# UD3_1_Gate_Driver.net
KiCad netlist of a schematic drawn in Altium Designer
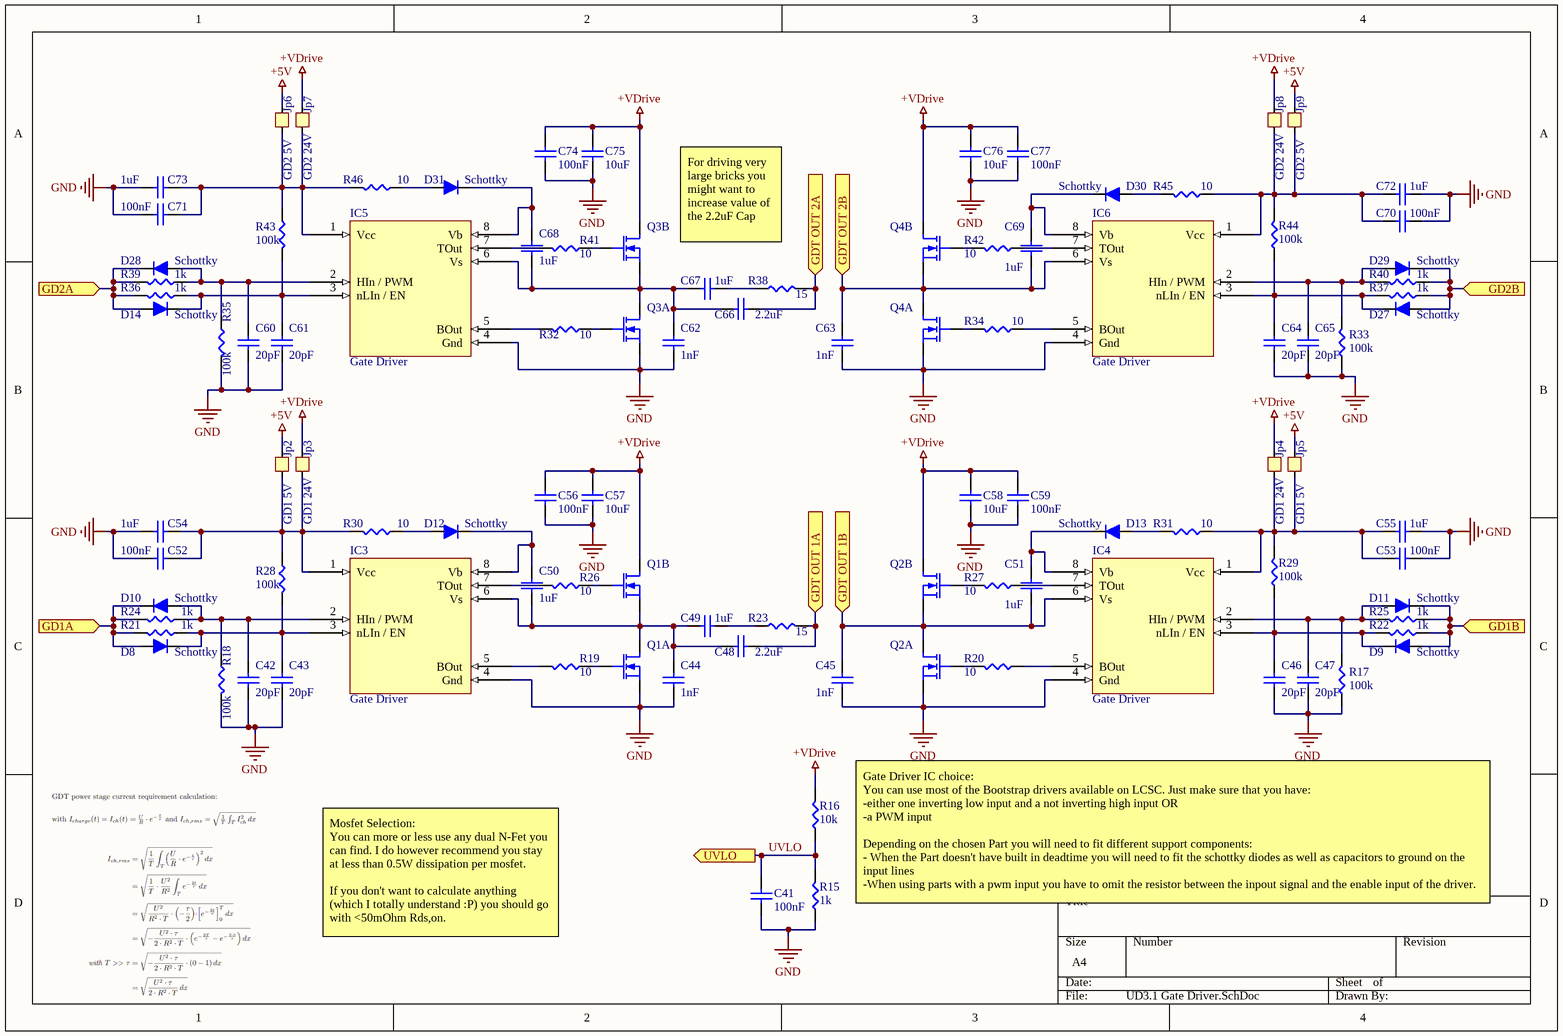
[diagram p0: UD3.1 Gate Driver.SchDoc]

(export (version "E")
  (design (tool "Eeschema 10.0.6"))
  (components
    (comp (ref "C41") (value "100nF") (footprint "0603") (libsource (lib "stdLib") (part "Cap")))
    (comp (ref "C42") (value "20pF") (footprint "0603") (libsource (lib "stdLib") (part "Cap")))
    (comp (ref "C43") (value "20pF") (footprint "0603") (libsource (lib "stdLib") (part "Cap")))
    (comp (ref "C44") (value "1nF") (footprint "0805") (libsource (lib "stdLib") (part "Cap")))
    (comp (ref "C45") (value "1nF") (footprint "0805") (libsource (lib "stdLib") (part "Cap")))
    (comp (ref "C46") (value "20pF") (footprint "0603") (libsource (lib "stdLib") (part "Cap")))
    (comp (ref "C47") (value "20pF") (footprint "0603") (libsource (lib "stdLib") (part "Cap")))
    (comp (ref "C48") (value "2.2uF") (footprint "1206") (libsource (lib "stdLib") (part "Cap")))
    (comp (ref "C49") (value "1uF") (footprint "1206") (libsource (lib "stdLib") (part "Cap")))
    (comp (ref "C50") (value "1uF") (footprint "0805") (libsource (lib "stdLib") (part "Cap")))
    (comp (ref "C51") (value "1uF") (footprint "0805") (libsource (lib "stdLib") (part "Cap")))
    (comp (ref "C52") (value "100nF") (footprint "0805") (libsource (lib "stdLib") (part "Cap")))
    (comp (ref "C53") (value "100nF") (footprint "0805") (libsource (lib "stdLib") (part "Cap")))
    (comp (ref "C54") (value "1uF") (footprint "0805") (libsource (lib "stdLib") (part "Cap")))
    (comp (ref "C55") (value "1uF") (footprint "0805") (libsource (lib "stdLib") (part "Cap")))
    (comp (ref "C56") (value "100nF") (footprint "0805") (libsource (lib "stdLib") (part "Cap")))
    (comp (ref "C57") (value "10uF") (footprint "0805") (libsource (lib "stdLib") (part "Cap")))
    (comp (ref "C58") (value "10uF") (footprint "0805") (libsource (lib "stdLib") (part "Cap")))
    (comp (ref "C59") (value "100nF") (footprint "0805") (libsource (lib "stdLib") (part "Cap")))
    (comp (ref "C60") (value "20pF") (footprint "0603") (libsource (lib "stdLib") (part "Cap")))
    (comp (ref "C61") (value "20pF") (footprint "0603") (libsource (lib "stdLib") (part "Cap")))
    (comp (ref "C62") (value "1nF") (footprint "0805") (libsource (lib "stdLib") (part "Cap")))
    (comp (ref "C63") (value "1nF") (footprint "0805") (libsource (lib "stdLib") (part "Cap")))
    (comp (ref "C64") (value "20pF") (footprint "0603") (libsource (lib "stdLib") (part "Cap")))
    (comp (ref "C65") (value "20pF") (footprint "0603") (libsource (lib "stdLib") (part "Cap")))
    (comp (ref "C66") (value "2.2uF") (footprint "1206") (libsource (lib "stdLib") (part "Cap")))
    (comp (ref "C67") (value "1uF") (footprint "1206") (libsource (lib "stdLib") (part "Cap")))
    (comp (ref "C68") (value "1uF") (footprint "0805") (libsource (lib "stdLib") (part "Cap")))
    (comp (ref "C69") (value "1uF") (footprint "0805") (libsource (lib "stdLib") (part "Cap")))
    (comp (ref "C70") (value "100nF") (footprint "0805") (libsource (lib "stdLib") (part "Cap")))
    (comp (ref "C71") (value "100nF") (footprint "0805") (libsource (lib "stdLib") (part "Cap")))
    (comp (ref "C72") (value "1uF") (footprint "0805") (libsource (lib "stdLib") (part "Cap")))
    (comp (ref "C73") (value "1uF") (footprint "0805") (libsource (lib "stdLib") (part "Cap")))
    (comp (ref "C74") (value "100nF") (footprint "0805") (libsource (lib "stdLib") (part "Cap")))
    (comp (ref "C75") (value "10uF") (footprint "0805") (libsource (lib "stdLib") (part "Cap")))
    (comp (ref "C76") (value "10uF") (footprint "0805") (libsource (lib "stdLib") (part "Cap")))
    (comp (ref "C77") (value "100nF") (footprint "0805") (libsource (lib "stdLib") (part "Cap")))
    (comp (ref "D8")
      (value "Schottky")
      (footprint "SOD523")
      (description "Cmon its a diode what more do I need to say?")
      (libsource (lib "stdLib") (part "Diode"))
    )
    (comp (ref "D9")
      (value "Schottky")
      (footprint "SOD523")
      (description "Cmon its a diode what more do I need to say?")
      (libsource (lib "stdLib") (part "Diode"))
    )
    (comp (ref "D10")
      (value "Schottky")
      (footprint "SOD523")
      (description "Cmon its a diode what more do I need to say?")
      (libsource (lib "stdLib") (part "Diode"))
    )
    (comp (ref "D11")
      (value "Schottky")
      (footprint "SOD523")
      (description "Cmon its a diode what more do I need to say?")
      (libsource (lib "stdLib") (part "Diode"))
    )
    (comp (ref "D12")
      (value "Schottky")
      (footprint "SOD523")
      (description "Cmon its a diode what more do I need to say?")
      (libsource (lib "stdLib") (part "Diode"))
    )
    (comp (ref "D13")
      (value "Schottky")
      (footprint "SOD523")
      (description "Cmon its a diode what more do I need to say?")
      (libsource (lib "stdLib") (part "Diode"))
    )
    (comp (ref "D14")
      (value "Schottky")
      (footprint "SOD523")
      (description "Cmon its a diode what more do I need to say?")
      (libsource (lib "stdLib") (part "Diode"))
    )
    (comp (ref "D27")
      (value "Schottky")
      (footprint "SOD523")
      (description "Cmon its a diode what more do I need to say?")
      (libsource (lib "stdLib") (part "Diode"))
    )
    (comp (ref "D28")
      (value "Schottky")
      (footprint "SOD523")
      (description "Cmon its a diode what more do I need to say?")
      (libsource (lib "stdLib") (part "Diode"))
    )
    (comp (ref "D29")
      (value "Schottky")
      (footprint "SOD523")
      (description "Cmon its a diode what more do I need to say?")
      (libsource (lib "stdLib") (part "Diode"))
    )
    (comp (ref "D30")
      (value "Schottky")
      (footprint "SOD523")
      (description "Cmon its a diode what more do I need to say?")
      (libsource (lib "stdLib") (part "Diode"))
    )
    (comp (ref "D31")
      (value "Schottky")
      (footprint "SOD523")
      (description "Cmon its a diode what more do I need to say?")
      (libsource (lib "stdLib") (part "Diode"))
    )
    (comp (ref "IC3")
      (value "Gate Driver")
      (footprint "SOIC8")
      (description "Bootstrappable half bridge driver IC")
      (libsource (lib "") (part "Gatedriver Bootstrap_1"))
    )
    (comp (ref "IC4")
      (value "Gate Driver")
      (footprint "SOIC8")
      (description "Bootstrappable half bridge driver IC")
      (libsource (lib "stdLib") (part "Gatedriver Bootstrap"))
    )
    (comp (ref "IC5")
      (value "Gate Driver")
      (footprint "SOIC8")
      (description "Bootstrappable half bridge driver IC")
      (libsource (lib "") (part "Gatedriver Bootstrap_1"))
    )
    (comp (ref "IC6")
      (value "Gate Driver")
      (footprint "SOIC8")
      (description "Bootstrappable half bridge driver IC")
      (libsource (lib "stdLib") (part "Gatedriver Bootstrap"))
    )
    (comp (ref "Jp2") (value "GD1 5V") (footprint "PCB Jumper NO") (libsource (lib "stdLib") (part "Jumper")))
    (comp (ref "Jp3")
      (value "GD1 24V")
      (footprint "PCB Jumper NO")
      (libsource (lib "stdLib") (part "Jumper"))
    )
    (comp (ref "Jp4") (value "GD1 24V") (footprint "PCB Jumper NO") (libsource (lib "") (part "Jumper_1")))
    (comp (ref "Jp5") (value "GD1 5V") (footprint "PCB Jumper NO") (libsource (lib "") (part "Jumper_1")))
    (comp (ref "Jp6") (value "GD2 5V") (footprint "PCB Jumper NO") (libsource (lib "stdLib") (part "Jumper")))
    (comp (ref "Jp7")
      (value "GD2 24V")
      (footprint "PCB Jumper NO")
      (libsource (lib "stdLib") (part "Jumper"))
    )
    (comp (ref "Jp8") (value "GD2 24V") (footprint "PCB Jumper NO") (libsource (lib "") (part "Jumper_1")))
    (comp (ref "Jp9") (value "GD2 5V") (footprint "PCB Jumper NO") (libsource (lib "") (part "Jumper_1")))
    (comp (ref "Q1")
      (value "Dual NFet")
      (footprint "SO-8FL - Dual")
      (description "Dual Mosfet, two N channel")
      (libsource (lib "stdLib") (part "Mosfet 2N"))
    )
    (comp (ref "Q2")
      (value "Dual NFet")
      (footprint "SO-8FL - Dual")
      (description "Dual Mosfet, two N channel")
      (libsource (lib "stdLib") (part "Mosfet 2N"))
    )
    (comp (ref "Q3")
      (value "Dual NFet")
      (footprint "SO-8FL - Dual")
      (description "Dual Mosfet, two N channel")
      (libsource (lib "stdLib") (part "Mosfet 2N"))
    )
    (comp (ref "Q4")
      (value "Dual NFet")
      (footprint "SO-8FL - Dual")
      (description "Dual Mosfet, two N channel")
      (libsource (lib "stdLib") (part "Mosfet 2N"))
    )
    (comp (ref "R15") (value "1k") (footprint "0603") (libsource (lib "stdLib") (part "Resistor")))
    (comp (ref "R16") (value "10k") (footprint "0603") (libsource (lib "stdLib") (part "Resistor")))
    (comp (ref "R17") (value "100k") (footprint "0603") (libsource (lib "stdLib") (part "Resistor")))
    (comp (ref "R18") (value "100k") (footprint "0603") (libsource (lib "stdLib") (part "Resistor")))
    (comp (ref "R19") (value "10") (footprint "0805") (libsource (lib "stdLib") (part "Resistor")))
    (comp (ref "R20") (value "10") (footprint "0805") (libsource (lib "stdLib") (part "Resistor")))
    (comp (ref "R21") (value "1k") (footprint "0603") (libsource (lib "stdLib") (part "Resistor")))
    (comp (ref "R22") (value "1k") (footprint "0603") (libsource (lib "stdLib") (part "Resistor")))
    (comp (ref "R23") (value "15") (footprint "1206") (libsource (lib "stdLib") (part "Resistor")))
    (comp (ref "R24") (value "1k") (footprint "0603") (libsource (lib "stdLib") (part "Resistor")))
    (comp (ref "R25") (value "1k") (footprint "0603") (libsource (lib "stdLib") (part "Resistor")))
    (comp (ref "R26") (value "10") (footprint "0805") (libsource (lib "stdLib") (part "Resistor")))
    (comp (ref "R27") (value "10") (footprint "0805") (libsource (lib "stdLib") (part "Resistor")))
    (comp (ref "R28") (value "100k") (footprint "0603") (libsource (lib "stdLib") (part "Resistor")))
    (comp (ref "R29") (value "100k") (footprint "0603") (libsource (lib "stdLib") (part "Resistor")))
    (comp (ref "R30") (value "10") (footprint "0603") (libsource (lib "stdLib") (part "Resistor")))
    (comp (ref "R31") (value "10") (footprint "0603") (libsource (lib "stdLib") (part "Resistor")))
    (comp (ref "R32") (value "10") (footprint "0805") (libsource (lib "stdLib") (part "Resistor")))
    (comp (ref "R33") (value "100k") (footprint "0603") (libsource (lib "stdLib") (part "Resistor")))
    (comp (ref "R34") (value "10") (footprint "0805") (libsource (lib "stdLib") (part "Resistor")))
    (comp (ref "R35") (value "100k") (footprint "0603") (libsource (lib "stdLib") (part "Resistor")))
    (comp (ref "R36") (value "1k") (footprint "0603") (libsource (lib "stdLib") (part "Resistor")))
    (comp (ref "R37") (value "1k") (footprint "0603") (libsource (lib "stdLib") (part "Resistor")))
    (comp (ref "R38") (value "15") (footprint "1206") (libsource (lib "stdLib") (part "Resistor")))
    (comp (ref "R39") (value "1k") (footprint "0603") (libsource (lib "stdLib") (part "Resistor")))
    (comp (ref "R40") (value "1k") (footprint "0603") (libsource (lib "stdLib") (part "Resistor")))
    (comp (ref "R41") (value "10") (footprint "0805") (libsource (lib "stdLib") (part "Resistor")))
    (comp (ref "R42") (value "10") (footprint "0805") (libsource (lib "stdLib") (part "Resistor")))
    (comp (ref "R43") (value "100k") (footprint "0603") (libsource (lib "stdLib") (part "Resistor")))
    (comp (ref "R44") (value "100k") (footprint "0603") (libsource (lib "stdLib") (part "Resistor")))
    (comp (ref "R45") (value "10") (footprint "0603") (libsource (lib "stdLib") (part "Resistor")))
    (comp (ref "R46") (value "10") (footprint "0603") (libsource (lib "stdLib") (part "Resistor")))
  )
  (nets
    (net (code "1") (name "+5V") (class "Default")
      (node (ref "Jp2") (pin "2") (pinfunction "2_2") (pintype "passive"))
      (node (ref "Jp5") (pin "2") (pinfunction "2_2") (pintype "passive"))
      (node (ref "Jp6") (pin "2") (pinfunction "2_2") (pintype "passive"))
      (node (ref "Jp9") (pin "2") (pinfunction "2_2") (pintype "passive"))
    )
    (net (code "2") (name "+VDrive") (class "Default")
      (node (ref "C56") (pin "2") (pinfunction "2_2") (pintype "passive"))
      (node (ref "C57") (pin "2") (pinfunction "2_2") (pintype "passive"))
      (node (ref "C58") (pin "2") (pinfunction "2_2") (pintype "passive"))
      (node (ref "C59") (pin "2") (pinfunction "2_2") (pintype "passive"))
      (node (ref "C74") (pin "2") (pinfunction "2_2") (pintype "passive"))
      (node (ref "C75") (pin "2") (pinfunction "2_2") (pintype "passive"))
      (node (ref "C76") (pin "2") (pinfunction "2_2") (pintype "passive"))
      (node (ref "C77") (pin "2") (pinfunction "2_2") (pintype "passive"))
      (node (ref "Jp3") (pin "2") (pinfunction "2_2") (pintype "passive"))
      (node (ref "Jp4") (pin "2") (pinfunction "2_2") (pintype "passive"))
      (node (ref "Jp7") (pin "2") (pinfunction "2_2") (pintype "passive"))
      (node (ref "Jp8") (pin "2") (pinfunction "2_2") (pintype "passive"))
      (node (ref "Q1") (pin "D1") (pinfunction "D1_D1") (pintype "passive"))
      (node (ref "Q2") (pin "D1") (pinfunction "D1_D1") (pintype "passive"))
      (node (ref "Q3") (pin "D1") (pinfunction "D1_D1") (pintype "passive"))
      (node (ref "Q4") (pin "D1") (pinfunction "D1_D1") (pintype "passive"))
      (node (ref "R16") (pin "1") (pinfunction "1_1") (pintype "passive"))
    )
    (net (code "3") (name "/GD1A") (class "Default")
      (node (ref "D10") (pin "2") (pintype "passive"))
      (node (ref "D8") (pin "1") (pintype "passive"))
      (node (ref "R21") (pin "1") (pinfunction "1_1") (pintype "passive"))
      (node (ref "R24") (pin "1") (pinfunction "1_1") (pintype "passive"))
    )
    (net (code "4") (name "/GD1B") (class "Default")
      (node (ref "D11") (pin "2") (pintype "passive"))
      (node (ref "D9") (pin "1") (pintype "passive"))
      (node (ref "R22") (pin "1") (pinfunction "1_1") (pintype "passive"))
      (node (ref "R25") (pin "1") (pinfunction "1_1") (pintype "passive"))
    )
    (net (code "5") (name "/GD2A") (class "Default")
      (node (ref "D14") (pin "1") (pintype "passive"))
      (node (ref "D28") (pin "2") (pintype "passive"))
      (node (ref "R36") (pin "1") (pinfunction "1_1") (pintype "passive"))
      (node (ref "R39") (pin "1") (pinfunction "1_1") (pintype "passive"))
    )
    (net (code "6") (name "/GD2B") (class "Default")
      (node (ref "D27") (pin "1") (pintype "passive"))
      (node (ref "D29") (pin "2") (pintype "passive"))
      (node (ref "R37") (pin "1") (pinfunction "1_1") (pintype "passive"))
      (node (ref "R40") (pin "1") (pinfunction "1_1") (pintype "passive"))
    )
    (net (code "7") (name "/GDT OUT 1A") (class "Default")
      (node (ref "C48") (pin "2") (pinfunction "2_2") (pintype "passive"))
      (node (ref "R23") (pin "2") (pinfunction "2_2") (pintype "passive"))
    )
    (net (code "8") (name "/GDT OUT 1B") (class "Default")
      (node (ref "C45") (pin "2") (pinfunction "2_2") (pintype "passive"))
      (node (ref "C51") (pin "1") (pinfunction "1_1") (pintype "passive"))
      (node (ref "IC4") (pin "6") (pinfunction "Vs_6") (pintype "input"))
      (node (ref "Q2") (pin "D2") (pinfunction "D2_D2") (pintype "passive"))
      (node (ref "Q2") (pin "S1") (pinfunction "S1_S1") (pintype "passive"))
    )
    (net (code "9") (name "/GDT OUT 2A") (class "Default")
      (node (ref "C66") (pin "2") (pinfunction "2_2") (pintype "passive"))
      (node (ref "R38") (pin "2") (pinfunction "2_2") (pintype "passive"))
    )
    (net (code "10") (name "/GDT OUT 2B") (class "Default")
      (node (ref "C63") (pin "2") (pinfunction "2_2") (pintype "passive"))
      (node (ref "C69") (pin "1") (pinfunction "1_1") (pintype "passive"))
      (node (ref "IC6") (pin "6") (pinfunction "Vs_6") (pintype "input"))
      (node (ref "Q4") (pin "D2") (pinfunction "D2_D2") (pintype "passive"))
      (node (ref "Q4") (pin "S1") (pinfunction "S1_S1") (pintype "passive"))
    )
    (net (code "11") (name "/UVLO") (class "Default")
      (node (ref "C41") (pin "2") (pinfunction "2_2") (pintype "passive"))
      (node (ref "R15") (pin "1") (pinfunction "1_1") (pintype "passive"))
      (node (ref "R16") (pin "2") (pinfunction "2_2") (pintype "passive"))
    )
    (net (code "12") (name "GND") (class "Default")
      (node (ref "C41") (pin "1") (pinfunction "1_1") (pintype "passive"))
      (node (ref "C42") (pin "2") (pinfunction "2_2") (pintype "passive"))
      (node (ref "C43") (pin "2") (pinfunction "2_2") (pintype "passive"))
      (node (ref "C44") (pin "1") (pinfunction "1_1") (pintype "passive"))
      (node (ref "C45") (pin "1") (pinfunction "1_1") (pintype "passive"))
      (node (ref "C46") (pin "2") (pinfunction "2_2") (pintype "passive"))
      (node (ref "C47") (pin "2") (pinfunction "2_2") (pintype "passive"))
      (node (ref "C52") (pin "2") (pinfunction "2_2") (pintype "passive"))
      (node (ref "C53") (pin "2") (pinfunction "2_2") (pintype "passive"))
      (node (ref "C54") (pin "2") (pinfunction "2_2") (pintype "passive"))
      (node (ref "C55") (pin "2") (pinfunction "2_2") (pintype "passive"))
      (node (ref "C56") (pin "1") (pinfunction "1_1") (pintype "passive"))
      (node (ref "C57") (pin "1") (pinfunction "1_1") (pintype "passive"))
      (node (ref "C58") (pin "1") (pinfunction "1_1") (pintype "passive"))
      (node (ref "C59") (pin "1") (pinfunction "1_1") (pintype "passive"))
      (node (ref "C60") (pin "2") (pinfunction "2_2") (pintype "passive"))
      (node (ref "C61") (pin "2") (pinfunction "2_2") (pintype "passive"))
      (node (ref "C62") (pin "1") (pinfunction "1_1") (pintype "passive"))
      (node (ref "C63") (pin "1") (pinfunction "1_1") (pintype "passive"))
      (node (ref "C64") (pin "2") (pinfunction "2_2") (pintype "passive"))
      (node (ref "C65") (pin "2") (pinfunction "2_2") (pintype "passive"))
      (node (ref "C70") (pin "2") (pinfunction "2_2") (pintype "passive"))
      (node (ref "C71") (pin "2") (pinfunction "2_2") (pintype "passive"))
      (node (ref "C72") (pin "2") (pinfunction "2_2") (pintype "passive"))
      (node (ref "C73") (pin "2") (pinfunction "2_2") (pintype "passive"))
      (node (ref "C74") (pin "1") (pinfunction "1_1") (pintype "passive"))
      (node (ref "C75") (pin "1") (pinfunction "1_1") (pintype "passive"))
      (node (ref "C76") (pin "1") (pinfunction "1_1") (pintype "passive"))
      (node (ref "C77") (pin "1") (pinfunction "1_1") (pintype "passive"))
      (node (ref "IC3") (pin "4") (pinfunction "Gnd_4") (pintype "input"))
      (node (ref "IC4") (pin "4") (pinfunction "Gnd_4") (pintype "input"))
      (node (ref "IC5") (pin "4") (pinfunction "Gnd_4") (pintype "input"))
      (node (ref "IC6") (pin "4") (pinfunction "Gnd_4") (pintype "input"))
      (node (ref "Q1") (pin "S2") (pinfunction "S2_S2") (pintype "passive"))
      (node (ref "Q2") (pin "S2") (pinfunction "S2_S2") (pintype "passive"))
      (node (ref "Q3") (pin "S2") (pinfunction "S2_S2") (pintype "passive"))
      (node (ref "Q4") (pin "S2") (pinfunction "S2_S2") (pintype "passive"))
      (node (ref "R15") (pin "2") (pinfunction "2_2") (pintype "passive"))
      (node (ref "R17") (pin "1") (pinfunction "1_1") (pintype "passive"))
      (node (ref "R18") (pin "1") (pinfunction "1_1") (pintype "passive"))
      (node (ref "R33") (pin "1") (pinfunction "1_1") (pintype "passive"))
      (node (ref "R35") (pin "1") (pinfunction "1_1") (pintype "passive"))
    )
    (net (code "13") (name "Net-(C49-Pad2)") (class "Default")
      (node (ref "C49") (pin "2") (pinfunction "2_2") (pintype "passive"))
      (node (ref "R23") (pin "1") (pinfunction "1_1") (pintype "passive"))
    )
    (net (code "14") (name "Net-(C67-Pad2)") (class "Default")
      (node (ref "C67") (pin "2") (pinfunction "2_2") (pintype "passive"))
      (node (ref "R38") (pin "1") (pinfunction "1_1") (pintype "passive"))
    )
    (net (code "15") (name "Net-(D12-Pad1)") (class "Default")
      (node (ref "D12") (pin "1") (pintype "passive"))
      (node (ref "R30") (pin "2") (pinfunction "2_2") (pintype "passive"))
    )
    (net (code "16") (name "Net-(D13-Pad1)") (class "Default")
      (node (ref "D13") (pin "1") (pintype "passive"))
      (node (ref "R31") (pin "2") (pinfunction "2_2") (pintype "passive"))
    )
    (net (code "17") (name "Net-(D30-Pad1)") (class "Default")
      (node (ref "D30") (pin "1") (pintype "passive"))
      (node (ref "R45") (pin "2") (pinfunction "2_2") (pintype "passive"))
    )
    (net (code "18") (name "Net-(D31-Pad1)") (class "Default")
      (node (ref "D31") (pin "1") (pintype "passive"))
      (node (ref "R46") (pin "2") (pinfunction "2_2") (pintype "passive"))
    )
    (net (code "19") (name "Net-(IC3-BOut)") (class "Default")
      (node (ref "IC3") (pin "5") (pinfunction "BOut_5") (pintype "input"))
      (node (ref "R19") (pin "1") (pinfunction "1_1") (pintype "passive"))
    )
    (net (code "20") (name "Net-(IC3-HIn_{slash}_PWM)") (class "Default")
      (node (ref "C42") (pin "1") (pinfunction "1_1") (pintype "passive"))
      (node (ref "D10") (pin "1") (pintype "passive"))
      (node (ref "IC3") (pin "2") (pinfunction "HIn_/_PWM_2") (pintype "input"))
      (node (ref "R18") (pin "2") (pinfunction "2_2") (pintype "passive"))
      (node (ref "R24") (pin "2") (pinfunction "2_2") (pintype "passive"))
    )
    (net (code "21") (name "Net-(IC3-TOut)") (class "Default")
      (node (ref "IC3") (pin "7") (pinfunction "TOut_7") (pintype "input"))
      (node (ref "R26") (pin "1") (pinfunction "1_1") (pintype "passive"))
    )
    (net (code "22") (name "Net-(IC3-Vb)") (class "Default")
      (node (ref "C50") (pin "2") (pinfunction "2_2") (pintype "passive"))
      (node (ref "D12") (pin "2") (pintype "passive"))
      (node (ref "IC3") (pin "8") (pinfunction "Vb_8") (pintype "input"))
    )
    (net (code "23") (name "Net-(IC3-Vcc)") (class "Default")
      (node (ref "C52") (pin "1") (pinfunction "1_1") (pintype "passive"))
      (node (ref "C54") (pin "1") (pinfunction "1_1") (pintype "passive"))
      (node (ref "IC3") (pin "1") (pinfunction "Vcc_1") (pintype "input"))
      (node (ref "Jp2") (pin "1") (pinfunction "1_1") (pintype "passive"))
      (node (ref "Jp3") (pin "1") (pinfunction "1_1") (pintype "passive"))
      (node (ref "R28") (pin "2") (pinfunction "2_2") (pintype "passive"))
      (node (ref "R30") (pin "1") (pinfunction "1_1") (pintype "passive"))
    )
    (net (code "24") (name "Net-(IC3-Vs)") (class "Default")
      (node (ref "C44") (pin "2") (pinfunction "2_2") (pintype "passive"))
      (node (ref "C48") (pin "1") (pinfunction "1_1") (pintype "passive"))
      (node (ref "C49") (pin "1") (pinfunction "1_1") (pintype "passive"))
      (node (ref "C50") (pin "1") (pinfunction "1_1") (pintype "passive"))
      (node (ref "IC3") (pin "6") (pinfunction "Vs_6") (pintype "input"))
      (node (ref "Q1") (pin "D2") (pinfunction "D2_D2") (pintype "passive"))
      (node (ref "Q1") (pin "S1") (pinfunction "S1_S1") (pintype "passive"))
    )
    (net (code "25") (name "Net-(IC3-nLIn_{slash}_EN)") (class "Default")
      (node (ref "C43") (pin "1") (pinfunction "1_1") (pintype "passive"))
      (node (ref "D8") (pin "2") (pintype "passive"))
      (node (ref "IC3") (pin "3") (pinfunction "nLIn_/_EN_3") (pintype "input"))
      (node (ref "R21") (pin "2") (pinfunction "2_2") (pintype "passive"))
      (node (ref "R28") (pin "1") (pinfunction "1_1") (pintype "passive"))
    )
    (net (code "26") (name "Net-(IC4-BOut)") (class "Default")
      (node (ref "IC4") (pin "5") (pinfunction "BOut_5") (pintype "input"))
      (node (ref "R20") (pin "1") (pinfunction "1_1") (pintype "passive"))
    )
    (net (code "27") (name "Net-(IC4-HIn_{slash}_PWM)") (class "Default")
      (node (ref "C47") (pin "1") (pinfunction "1_1") (pintype "passive"))
      (node (ref "D11") (pin "1") (pintype "passive"))
      (node (ref "IC4") (pin "2") (pinfunction "HIn_/_PWM_2") (pintype "input"))
      (node (ref "R17") (pin "2") (pinfunction "2_2") (pintype "passive"))
      (node (ref "R25") (pin "2") (pinfunction "2_2") (pintype "passive"))
    )
    (net (code "28") (name "Net-(IC4-TOut)") (class "Default")
      (node (ref "IC4") (pin "7") (pinfunction "TOut_7") (pintype "input"))
      (node (ref "R27") (pin "1") (pinfunction "1_1") (pintype "passive"))
    )
    (net (code "29") (name "Net-(IC4-Vb)") (class "Default")
      (node (ref "C51") (pin "2") (pinfunction "2_2") (pintype "passive"))
      (node (ref "D13") (pin "2") (pintype "passive"))
      (node (ref "IC4") (pin "8") (pinfunction "Vb_8") (pintype "input"))
    )
    (net (code "30") (name "Net-(IC4-Vcc)") (class "Default")
      (node (ref "C53") (pin "1") (pinfunction "1_1") (pintype "passive"))
      (node (ref "C55") (pin "1") (pinfunction "1_1") (pintype "passive"))
      (node (ref "IC4") (pin "1") (pinfunction "Vcc_1") (pintype "input"))
      (node (ref "Jp4") (pin "1") (pinfunction "1_1") (pintype "passive"))
      (node (ref "Jp5") (pin "1") (pinfunction "1_1") (pintype "passive"))
      (node (ref "R29") (pin "2") (pinfunction "2_2") (pintype "passive"))
      (node (ref "R31") (pin "1") (pinfunction "1_1") (pintype "passive"))
    )
    (net (code "31") (name "Net-(IC4-nLIn_{slash}_EN)") (class "Default")
      (node (ref "C46") (pin "1") (pinfunction "1_1") (pintype "passive"))
      (node (ref "D9") (pin "2") (pintype "passive"))
      (node (ref "IC4") (pin "3") (pinfunction "nLIn_/_EN_3") (pintype "input"))
      (node (ref "R22") (pin "2") (pinfunction "2_2") (pintype "passive"))
      (node (ref "R29") (pin "1") (pinfunction "1_1") (pintype "passive"))
    )
    (net (code "32") (name "Net-(IC5-BOut)") (class "Default")
      (node (ref "IC5") (pin "5") (pinfunction "BOut_5") (pintype "input"))
      (node (ref "R32") (pin "1") (pinfunction "1_1") (pintype "passive"))
    )
    (net (code "33") (name "Net-(IC5-HIn_{slash}_PWM)") (class "Default")
      (node (ref "C60") (pin "1") (pinfunction "1_1") (pintype "passive"))
      (node (ref "D28") (pin "1") (pintype "passive"))
      (node (ref "IC5") (pin "2") (pinfunction "HIn_/_PWM_2") (pintype "input"))
      (node (ref "R35") (pin "2") (pinfunction "2_2") (pintype "passive"))
      (node (ref "R39") (pin "2") (pinfunction "2_2") (pintype "passive"))
    )
    (net (code "34") (name "Net-(IC5-TOut)") (class "Default")
      (node (ref "IC5") (pin "7") (pinfunction "TOut_7") (pintype "input"))
      (node (ref "R41") (pin "1") (pinfunction "1_1") (pintype "passive"))
    )
    (net (code "35") (name "Net-(IC5-Vb)") (class "Default")
      (node (ref "C68") (pin "2") (pinfunction "2_2") (pintype "passive"))
      (node (ref "D31") (pin "2") (pintype "passive"))
      (node (ref "IC5") (pin "8") (pinfunction "Vb_8") (pintype "input"))
    )
    (net (code "36") (name "Net-(IC5-Vcc)") (class "Default")
      (node (ref "C71") (pin "1") (pinfunction "1_1") (pintype "passive"))
      (node (ref "C73") (pin "1") (pinfunction "1_1") (pintype "passive"))
      (node (ref "IC5") (pin "1") (pinfunction "Vcc_1") (pintype "input"))
      (node (ref "Jp6") (pin "1") (pinfunction "1_1") (pintype "passive"))
      (node (ref "Jp7") (pin "1") (pinfunction "1_1") (pintype "passive"))
      (node (ref "R43") (pin "2") (pinfunction "2_2") (pintype "passive"))
      (node (ref "R46") (pin "1") (pinfunction "1_1") (pintype "passive"))
    )
    (net (code "37") (name "Net-(IC5-Vs)") (class "Default")
      (node (ref "C62") (pin "2") (pinfunction "2_2") (pintype "passive"))
      (node (ref "C66") (pin "1") (pinfunction "1_1") (pintype "passive"))
      (node (ref "C67") (pin "1") (pinfunction "1_1") (pintype "passive"))
      (node (ref "C68") (pin "1") (pinfunction "1_1") (pintype "passive"))
      (node (ref "IC5") (pin "6") (pinfunction "Vs_6") (pintype "input"))
      (node (ref "Q3") (pin "D2") (pinfunction "D2_D2") (pintype "passive"))
      (node (ref "Q3") (pin "S1") (pinfunction "S1_S1") (pintype "passive"))
    )
    (net (code "38") (name "Net-(IC5-nLIn_{slash}_EN)") (class "Default")
      (node (ref "C61") (pin "1") (pinfunction "1_1") (pintype "passive"))
      (node (ref "D14") (pin "2") (pintype "passive"))
      (node (ref "IC5") (pin "3") (pinfunction "nLIn_/_EN_3") (pintype "input"))
      (node (ref "R36") (pin "2") (pinfunction "2_2") (pintype "passive"))
      (node (ref "R43") (pin "1") (pinfunction "1_1") (pintype "passive"))
    )
    (net (code "39") (name "Net-(IC6-BOut)") (class "Default")
      (node (ref "IC6") (pin "5") (pinfunction "BOut_5") (pintype "input"))
      (node (ref "R34") (pin "1") (pinfunction "1_1") (pintype "passive"))
    )
    (net (code "40") (name "Net-(IC6-HIn_{slash}_PWM)") (class "Default")
      (node (ref "C65") (pin "1") (pinfunction "1_1") (pintype "passive"))
      (node (ref "D29") (pin "1") (pintype "passive"))
      (node (ref "IC6") (pin "2") (pinfunction "HIn_/_PWM_2") (pintype "input"))
      (node (ref "R33") (pin "2") (pinfunction "2_2") (pintype "passive"))
      (node (ref "R40") (pin "2") (pinfunction "2_2") (pintype "passive"))
    )
    (net (code "41") (name "Net-(IC6-TOut)") (class "Default")
      (node (ref "IC6") (pin "7") (pinfunction "TOut_7") (pintype "input"))
      (node (ref "R42") (pin "1") (pinfunction "1_1") (pintype "passive"))
    )
    (net (code "42") (name "Net-(IC6-Vb)") (class "Default")
      (node (ref "C69") (pin "2") (pinfunction "2_2") (pintype "passive"))
      (node (ref "D30") (pin "2") (pintype "passive"))
      (node (ref "IC6") (pin "8") (pinfunction "Vb_8") (pintype "input"))
    )
    (net (code "43") (name "Net-(IC6-Vcc)") (class "Default")
      (node (ref "C70") (pin "1") (pinfunction "1_1") (pintype "passive"))
      (node (ref "C72") (pin "1") (pinfunction "1_1") (pintype "passive"))
      (node (ref "IC6") (pin "1") (pinfunction "Vcc_1") (pintype "input"))
      (node (ref "Jp8") (pin "1") (pinfunction "1_1") (pintype "passive"))
      (node (ref "Jp9") (pin "1") (pinfunction "1_1") (pintype "passive"))
      (node (ref "R44") (pin "2") (pinfunction "2_2") (pintype "passive"))
      (node (ref "R45") (pin "1") (pinfunction "1_1") (pintype "passive"))
    )
    (net (code "44") (name "Net-(IC6-nLIn_{slash}_EN)") (class "Default")
      (node (ref "C64") (pin "1") (pinfunction "1_1") (pintype "passive"))
      (node (ref "D27") (pin "2") (pintype "passive"))
      (node (ref "IC6") (pin "3") (pinfunction "nLIn_/_EN_3") (pintype "input"))
      (node (ref "R37") (pin "2") (pinfunction "2_2") (pintype "passive"))
      (node (ref "R44") (pin "1") (pinfunction "1_1") (pintype "passive"))
    )
    (net (code "45") (name "Net-(Q1-PadG1)") (class "Default")
      (node (ref "Q1") (pin "G1") (pinfunction "G1_G1") (pintype "passive"))
      (node (ref "R26") (pin "2") (pinfunction "2_2") (pintype "passive"))
    )
    (net (code "46") (name "Net-(Q1-PadG2)") (class "Default")
      (node (ref "Q1") (pin "G2") (pinfunction "G2_G2") (pintype "passive"))
      (node (ref "R19") (pin "2") (pinfunction "2_2") (pintype "passive"))
    )
    (net (code "47") (name "Net-(Q2-PadG1)") (class "Default")
      (node (ref "Q2") (pin "G1") (pinfunction "G1_G1") (pintype "passive"))
      (node (ref "R27") (pin "2") (pinfunction "2_2") (pintype "passive"))
    )
    (net (code "48") (name "Net-(Q2-PadG2)") (class "Default")
      (node (ref "Q2") (pin "G2") (pinfunction "G2_G2") (pintype "passive"))
      (node (ref "R20") (pin "2") (pinfunction "2_2") (pintype "passive"))
    )
    (net (code "49") (name "Net-(Q3-PadG1)") (class "Default")
      (node (ref "Q3") (pin "G1") (pinfunction "G1_G1") (pintype "passive"))
      (node (ref "R41") (pin "2") (pinfunction "2_2") (pintype "passive"))
    )
    (net (code "50") (name "Net-(Q3-PadG2)") (class "Default")
      (node (ref "Q3") (pin "G2") (pinfunction "G2_G2") (pintype "passive"))
      (node (ref "R32") (pin "2") (pinfunction "2_2") (pintype "passive"))
    )
    (net (code "51") (name "Net-(Q4-PadG1)") (class "Default")
      (node (ref "Q4") (pin "G1") (pinfunction "G1_G1") (pintype "passive"))
      (node (ref "R42") (pin "2") (pinfunction "2_2") (pintype "passive"))
    )
    (net (code "52") (name "Net-(Q4-PadG2)") (class "Default")
      (node (ref "Q4") (pin "G2") (pinfunction "G2_G2") (pintype "passive"))
      (node (ref "R34") (pin "2") (pinfunction "2_2") (pintype "passive"))
    )
  )
)
